# MCU.net
KiCad netlist of a schematic drawn in Altium Designer
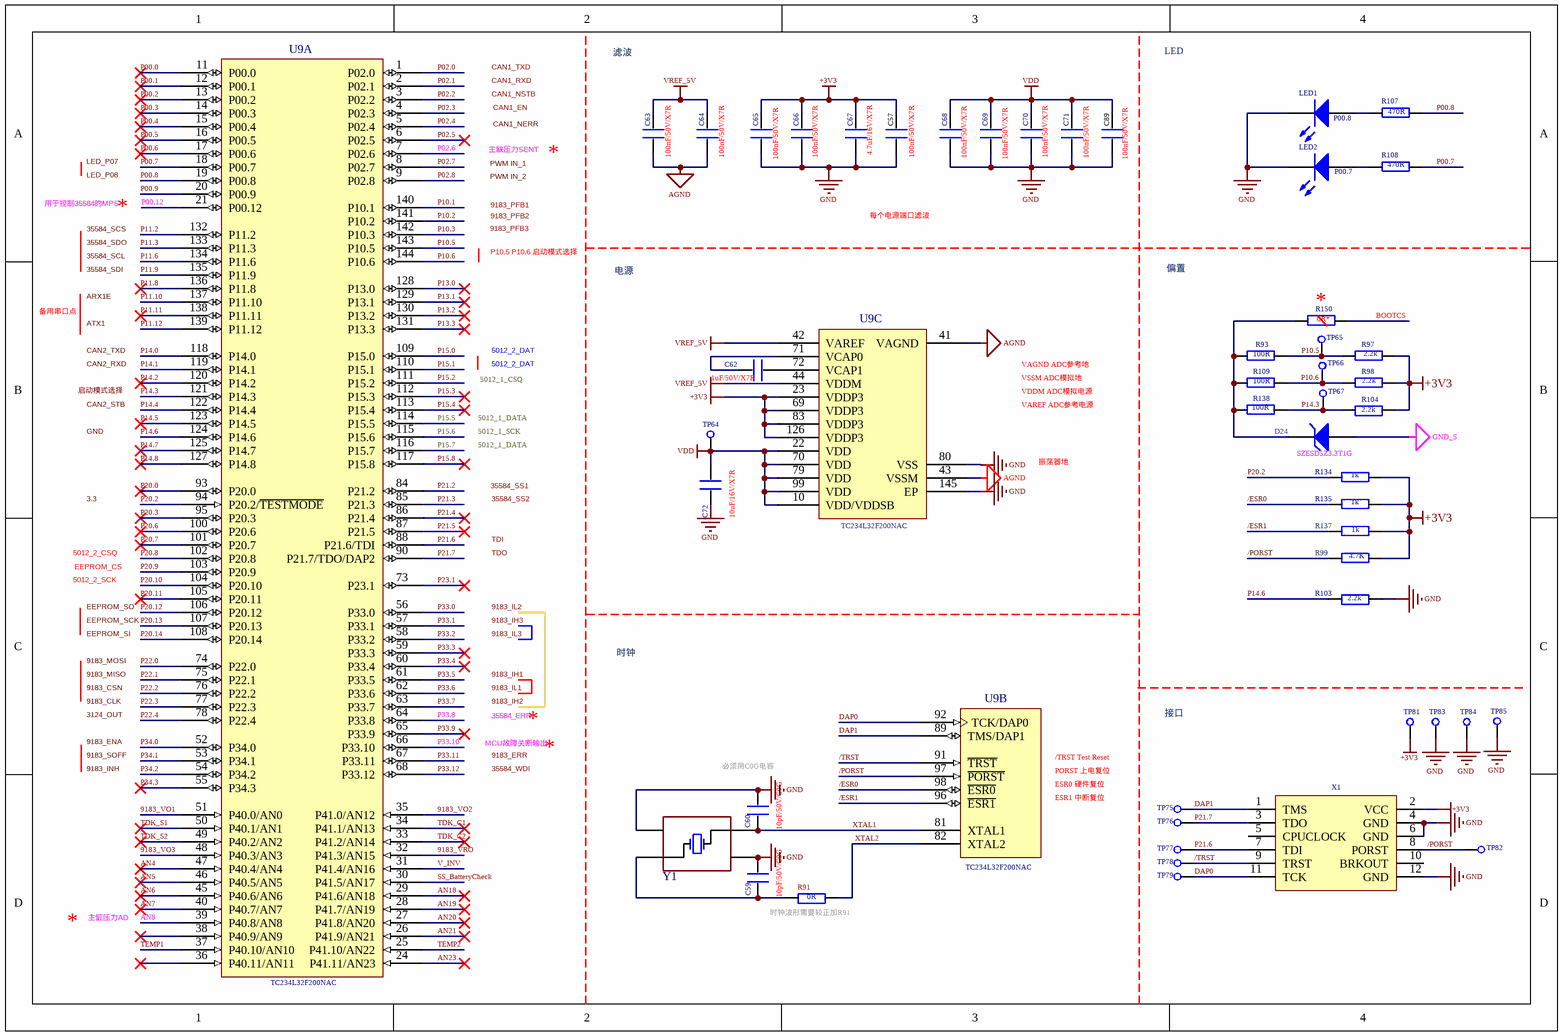
[diagram p0: MCU.SchDoc]

(export (version "E")
  (design (tool "Eeschema 10.0.6"))
  (components
    (comp (ref "C57")
      (value "100nF/50V/X7R")
      (footprint "C0603P")
      (libsource (lib "WarShip V3 STM32103封装库") (part "C"))
    )
    (comp (ref "C59")
      (value "10pF/50V/C0G")
      (footprint "C0603P")
      (libsource (lib "WarShip V3 STM32103封装库") (part "C"))
    )
    (comp (ref "C60")
      (value "10pF/50V/C0G")
      (footprint "C0603P")
      (libsource (lib "WarShip V3 STM32103封装库") (part "C"))
    )
    (comp (ref "C62")
      (value "1uF/50V/X7R")
      (footprint "C0805")
      (libsource (lib "WarShip V3 STM32103封装库") (part "C"))
    )
    (comp (ref "C63")
      (value "100nF/50V/X7R")
      (footprint "C0603P")
      (libsource (lib "WarShip V3 STM32103封装库") (part "C"))
    )
    (comp (ref "C64")
      (value "100nF/50V/X7R")
      (footprint "IEBS_V1.4:C0603P")
      (libsource (lib "WarShip V3 STM32103封装库") (part "C"))
    )
    (comp (ref "C65")
      (value "100nF/50V/X7R")
      (footprint "C0603P")
      (libsource (lib "WarShip V3 STM32103封装库") (part "C"))
    )
    (comp (ref "C66")
      (value "100nF/50V/X7R")
      (footprint "C0603P")
      (libsource (lib "WarShip V3 STM32103封装库") (part "C"))
    )
    (comp (ref "C67")
      (value "4.7uF/16V/X7R")
      (footprint "C0805")
      (libsource (lib "WarShip V3 STM32103封装库") (part "C"))
    )
    (comp (ref "C68")
      (value "100nF/50V/X7R")
      (footprint "C0603P")
      (libsource (lib "WarShip V3 STM32103封装库") (part "C"))
    )
    (comp (ref "C69")
      (value "100nF/50V/X7R")
      (footprint "C0603P")
      (libsource (lib "WarShip V3 STM32103封装库") (part "C"))
    )
    (comp (ref "C70")
      (value "100nF/50V/X7R")
      (footprint "C0603P")
      (libsource (lib "WarShip V3 STM32103封装库") (part "C"))
    )
    (comp (ref "C71")
      (value "100nF/50V/X7R")
      (footprint "C0603P")
      (libsource (lib "WarShip V3 STM32103封装库") (part "C"))
    )
    (comp (ref "C72")
      (value "10uF/16V/X7R")
      (footprint "C1206")
      (libsource (lib "WarShip V3 STM32103封装库") (part "C"))
    )
    (comp (ref "C89")
      (value "100nF/50V/X7R")
      (footprint "C0603P")
      (libsource (lib "WarShip V3 STM32103封装库") (part "C"))
    )
    (comp (ref "D24")
      (value "SZESD5Z3.3T1G")
      (footprint "SOD-523F")
      (description "Zener Diode")
      (fields (field (name "PUBLISHER") "Altium Limited"))
      (libsource (lib "Miscellaneous Devices") (part "D Zener"))
    )
    (comp (ref "LED1")
      (value "P00.8")
      (footprint "LED 0805")
      (description "Typical RED, GREEN, YELLOW, AMBER GaAs LED")
      (fields (field (name "PUBLISHER") "Altium Limited"))
      (libsource (lib "WarShip V3 STM32103封装库") (part "LED2"))
    )
    (comp (ref "LED2")
      (value "P00.7")
      (footprint "LED 0805")
      (description "Typical RED, GREEN, YELLOW, AMBER GaAs LED")
      (fields (field (name "PUBLISHER") "Altium Limited"))
      (libsource (lib "WarShip V3 STM32103封装库") (part "LED2"))
    )
    (comp (ref "R91") (value "0R") (footprint "0603P") (libsource (lib "WarShip V3 STM32103封装库") (part "R")))
    (comp (ref "R93")
      (value "100R")
      (footprint "0603P")
      (libsource (lib "WarShip V3 STM32103封装库") (part "R"))
    )
    (comp (ref "R97")
      (value "2.2k")
      (footprint "0603P")
      (libsource (lib "WarShip V3 STM32103封装库") (part "R"))
    )
    (comp (ref "R98")
      (value "2.2k")
      (footprint "0603P")
      (libsource (lib "WarShip V3 STM32103封装库") (part "R"))
    )
    (comp (ref "R99")
      (value "4.7K")
      (footprint "0603P")
      (libsource (lib "WarShip V3 STM32103封装库") (part "R"))
    )
    (comp (ref "R103")
      (value "2.2k")
      (footprint "0603P")
      (libsource (lib "WarShip V3 STM32103封装库") (part "R"))
    )
    (comp (ref "R104")
      (value "2.2k")
      (footprint "0603P")
      (libsource (lib "WarShip V3 STM32103封装库") (part "R"))
    )
    (comp (ref "R107")
      (value "470R")
      (footprint "0603P")
      (libsource (lib "WarShip V3 STM32103封装库") (part "R"))
    )
    (comp (ref "R108")
      (value "470R")
      (footprint "0603P")
      (libsource (lib "WarShip V3 STM32103封装库") (part "R"))
    )
    (comp (ref "R109")
      (value "100R")
      (footprint "0603P")
      (libsource (lib "WarShip V3 STM32103封装库") (part "R"))
    )
    (comp (ref "R134") (value "1k") (footprint "0603P") (libsource (lib "WarShip V3 STM32103封装库") (part "R")))
    (comp (ref "R135") (value "1k") (footprint "0603P") (libsource (lib "WarShip V3 STM32103封装库") (part "R")))
    (comp (ref "R137") (value "1k") (footprint "0603P") (libsource (lib "WarShip V3 STM32103封装库") (part "R")))
    (comp (ref "R138")
      (value "100R")
      (footprint "0603P")
      (libsource (lib "WarShip V3 STM32103封装库") (part "R"))
    )
    (comp (ref "R150")
      (value "0R*")
      (footprint "0603P")
      (libsource (lib "WarShip V3 STM32103封装库") (part "R"))
    )
    (comp (ref "TP64") (value "测试点") (footprint "测试点") (libsource (lib "yds") (part "测试点")))
    (comp (ref "TP65") (value "测试点") (footprint "测试点") (libsource (lib "yds") (part "测试点")))
    (comp (ref "TP66") (value "测试点") (footprint "测试点") (libsource (lib "yds") (part "测试点")))
    (comp (ref "TP67") (value "测试点") (footprint "测试点") (libsource (lib "yds") (part "测试点")))
    (comp (ref "TP75") (value "测试点") (footprint "测试点") (libsource (lib "yds") (part "测试点")))
    (comp (ref "TP76") (value "测试点") (footprint "测试点") (libsource (lib "yds") (part "测试点")))
    (comp (ref "TP77") (value "测试点") (footprint "测试点") (libsource (lib "yds") (part "测试点")))
    (comp (ref "TP78") (value "测试点") (footprint "测试点") (libsource (lib "yds") (part "测试点")))
    (comp (ref "TP79") (value "测试点") (footprint "测试点") (libsource (lib "yds") (part "测试点")))
    (comp (ref "TP81") (value "测试点") (footprint "测试点") (libsource (lib "yds") (part "测试点")))
    (comp (ref "TP82") (value "测试点") (footprint "测试点") (libsource (lib "yds") (part "测试点")))
    (comp (ref "TP83") (value "测试点") (footprint "测试点") (libsource (lib "yds") (part "测试点")))
    (comp (ref "TP84") (value "测试点") (footprint "测试点") (libsource (lib "yds") (part "测试点")))
    (comp (ref "TP85") (value "测试点") (footprint "测试点") (libsource (lib "yds") (part "测试点")))
    (comp (ref "U9")
      (value "TC234L32F200NAC")
      (footprint "INF-PG-TQFP-144-27_7500X7500TP_V")
      (fields (field (name "PARTNUMBER") "SAK-TC234LA-32F200F AB") (field (name "MANUFACTURER") "Infineon"))
      (libsource (lib "Infineon Microcontroller 32-bit TriCore AURIX") (part "SAK-TC234LA-32F200F AB"))
    )
    (comp (ref "X1") (value "12P") (footprint "HDR2X6 - duplicate") (libsource (lib "myTY") (part "12P")))
    (comp (ref "Y1") (value "晶振") (footprint "OSC-SMD_4P-L3.2-W2.5-BL") (libsource (lib "yds") (part "晶振")))
  )
  (nets
    (net (code "1") (name "+3V3") (class "Default")
      (node (ref "C57") (pin "1") (pintype "passive"))
      (node (ref "C65") (pin "1") (pintype "passive"))
      (node (ref "C66") (pin "1") (pintype "passive"))
      (node (ref "C67") (pin "2") (pintype "passive"))
      (node (ref "R104") (pin "2") (pintype "passive"))
      (node (ref "R134") (pin "1") (pintype "passive"))
      (node (ref "R135") (pin "1") (pintype "passive"))
      (node (ref "R137") (pin "1") (pintype "passive"))
      (node (ref "R97") (pin "1") (pintype "passive"))
      (node (ref "R98") (pin "1") (pintype "passive"))
      (node (ref "R99") (pin "1") (pintype "passive"))
      (node (ref "TP81") (pin "1") (pinfunction "1_1") (pintype "passive"))
      (node (ref "U9") (pin "126") (pinfunction "VDDP3_126") (pintype "power_in"))
      (node (ref "U9") (pin "23") (pinfunction "VDDP3_23") (pintype "power_in"))
      (node (ref "U9") (pin "69") (pinfunction "VDDP3_69") (pintype "power_in"))
      (node (ref "U9") (pin "83") (pinfunction "VDDP3_83") (pintype "power_in"))
      (node (ref "X1") (pin "2") (pinfunction "VCC_2") (pintype "passive"))
    )
    (net (code "5") (name "/9183_VO1") (class "Default")
      (node (ref "U9") (pin "51") (pinfunction "P40.0/AN0_51") (pintype "input"))
    )
    (net (code "6") (name "/9183_VO2") (class "Default")
      (node (ref "U9") (pin "35") (pinfunction "P41.0/AN12_35") (pintype "input"))
    )
    (net (code "7") (name "/9183_VO3") (class "Default")
      (node (ref "U9") (pin "48") (pinfunction "P40.3/AN3_48") (pintype "input"))
    )
    (net (code "8") (name "/9183_VRO") (class "Default")
      (node (ref "U9") (pin "32") (pinfunction "P41.3/AN15_32") (pintype "input"))
    )
    (net (code "9") (name "/AN4") (class "Default")
      (node (ref "U9") (pin "47") (pinfunction "P40.4/AN4_47") (pintype "input+no_connect"))
    )
    (net (code "10") (name "/AN5") (class "Default")
      (node (ref "U9") (pin "46") (pinfunction "P40.5/AN5_46") (pintype "input+no_connect"))
    )
    (net (code "11") (name "/AN6") (class "Default")
      (node (ref "U9") (pin "45") (pinfunction "P40.6/AN6_45") (pintype "input+no_connect"))
    )
    (net (code "12") (name "/AN7") (class "Default")
      (node (ref "U9") (pin "40") (pinfunction "P40.7/AN7_40") (pintype "input+no_connect"))
    )
    (net (code "13") (name "/AN8") (class "Default")
      (node (ref "U9") (pin "39") (pinfunction "P40.8/AN8_39") (pintype "input"))
    )
    (net (code "14") (name "/AN18") (class "Default")
      (node (ref "U9") (pin "29") (pinfunction "P41.6/AN18_29") (pintype "input+no_connect"))
    )
    (net (code "15") (name "/AN19") (class "Default")
      (node (ref "U9") (pin "28") (pinfunction "P41.7/AN19_28") (pintype "input+no_connect"))
    )
    (net (code "16") (name "/AN20") (class "Default")
      (node (ref "U9") (pin "27") (pinfunction "P41.8/AN20_27") (pintype "input+no_connect"))
    )
    (net (code "17") (name "/AN21") (class "Default")
      (node (ref "U9") (pin "26") (pinfunction "P41.9/AN21_26") (pintype "input+no_connect"))
    )
    (net (code "18") (name "/AN23") (class "Default")
      (node (ref "U9") (pin "24") (pinfunction "P41.11/AN23_24") (pintype "input+no_connect"))
    )
    (net (code "19") (name "/BOOTCS") (class "Default") (node (ref "R150") (pin "1") (pintype "passive")))
    (net (code "20") (name "/DAP0") (class "Default")
      (node (ref "TP79") (pin "1") (pinfunction "1_1") (pintype "passive"))
      (node (ref "U9") (pin "92") (pinfunction "TCK/DAP0_92") (pintype "input"))
      (node (ref "X1") (pin "11") (pinfunction "TCK_11") (pintype "passive"))
    )
    (net (code "21") (name "/DAP1") (class "Default")
      (node (ref "TP75") (pin "1") (pinfunction "1_1") (pintype "passive"))
      (node (ref "U9") (pin "89") (pinfunction "TMS/DAP1_89") (pintype "bidirectional"))
      (node (ref "X1") (pin "1") (pinfunction "TMS_1") (pintype "passive"))
    )
    (net (code "22") (name "/P00.0") (class "Default")
      (node (ref "U9") (pin "11") (pinfunction "P00.0_11") (pintype "bidirectional+no_connect"))
    )
    (net (code "23") (name "/P00.1") (class "Default")
      (node (ref "U9") (pin "12") (pinfunction "P00.1_12") (pintype "bidirectional+no_connect"))
    )
    (net (code "24") (name "/P00.2") (class "Default")
      (node (ref "U9") (pin "13") (pinfunction "P00.2_13") (pintype "bidirectional+no_connect"))
    )
    (net (code "25") (name "/P00.3") (class "Default")
      (node (ref "U9") (pin "14") (pinfunction "P00.3_14") (pintype "bidirectional+no_connect"))
    )
    (net (code "26") (name "/P00.4") (class "Default")
      (node (ref "U9") (pin "15") (pinfunction "P00.4_15") (pintype "bidirectional+no_connect"))
    )
    (net (code "27") (name "/P00.5") (class "Default")
      (node (ref "U9") (pin "16") (pinfunction "P00.5_16") (pintype "bidirectional+no_connect"))
    )
    (net (code "28") (name "/P00.6") (class "Default")
      (node (ref "U9") (pin "17") (pinfunction "P00.6_17") (pintype "bidirectional+no_connect"))
    )
    (net (code "29") (name "/P00.7") (class "Default")
      (node (ref "R108") (pin "1") (pintype "passive"))
      (node (ref "U9") (pin "18") (pinfunction "P00.7_18") (pintype "bidirectional"))
    )
    (net (code "30") (name "/P00.8") (class "Default")
      (node (ref "R107") (pin "1") (pintype "passive"))
      (node (ref "U9") (pin "19") (pinfunction "P00.8_19") (pintype "bidirectional"))
    )
    (net (code "31") (name "/P00.9") (class "Default")
      (node (ref "U9") (pin "20") (pinfunction "P00.9_20") (pintype "bidirectional"))
    )
    (net (code "32") (name "/P00.12") (class "Default")
      (node (ref "U9") (pin "21") (pinfunction "P00.12_21") (pintype "bidirectional"))
    )
    (net (code "33") (name "/P02.0") (class "Default")
      (node (ref "U9") (pin "1") (pinfunction "P02.0_1") (pintype "bidirectional"))
    )
    (net (code "34") (name "/P02.1") (class "Default")
      (node (ref "U9") (pin "2") (pinfunction "P02.1_2") (pintype "bidirectional"))
    )
    (net (code "35") (name "/P02.2") (class "Default")
      (node (ref "U9") (pin "3") (pinfunction "P02.2_3") (pintype "bidirectional"))
    )
    (net (code "36") (name "/P02.3") (class "Default")
      (node (ref "U9") (pin "4") (pinfunction "P02.3_4") (pintype "bidirectional"))
    )
    (net (code "37") (name "/P02.4") (class "Default")
      (node (ref "U9") (pin "5") (pinfunction "P02.4_5") (pintype "bidirectional"))
    )
    (net (code "38") (name "/P02.5") (class "Default")
      (node (ref "U9") (pin "6") (pinfunction "P02.5_6") (pintype "bidirectional+no_connect"))
    )
    (net (code "39") (name "/P02.6") (class "Default")
      (node (ref "U9") (pin "7") (pinfunction "P02.6_7") (pintype "bidirectional"))
    )
    (net (code "40") (name "/P02.7") (class "Default")
      (node (ref "U9") (pin "8") (pinfunction "P02.7_8") (pintype "bidirectional"))
    )
    (net (code "41") (name "/P02.8") (class "Default")
      (node (ref "U9") (pin "9") (pinfunction "P02.8_9") (pintype "bidirectional"))
    )
    (net (code "42") (name "/P10.1") (class "Default")
      (node (ref "U9") (pin "140") (pinfunction "P10.1_140") (pintype "bidirectional"))
    )
    (net (code "43") (name "/P10.2") (class "Default")
      (node (ref "U9") (pin "141") (pinfunction "P10.2_141") (pintype "bidirectional"))
    )
    (net (code "44") (name "/P10.3") (class "Default")
      (node (ref "U9") (pin "142") (pinfunction "P10.3_142") (pintype "bidirectional"))
    )
    (net (code "45") (name "/P10.5") (class "Default")
      (node (ref "R93") (pin "1") (pintype "passive"))
      (node (ref "R97") (pin "2") (pintype "passive"))
      (node (ref "TP65") (pin "1") (pinfunction "1_1") (pintype "passive"))
      (node (ref "U9") (pin "143") (pinfunction "P10.5_143") (pintype "bidirectional"))
    )
    (net (code "46") (name "/P10.6") (class "Default")
      (node (ref "R109") (pin "1") (pintype "passive"))
      (node (ref "R98") (pin "2") (pintype "passive"))
      (node (ref "TP66") (pin "1") (pinfunction "1_1") (pintype "passive"))
      (node (ref "U9") (pin "144") (pinfunction "P10.6_144") (pintype "bidirectional"))
    )
    (net (code "47") (name "/P11.2") (class "Default")
      (node (ref "U9") (pin "132") (pinfunction "P11.2_132") (pintype "bidirectional"))
    )
    (net (code "48") (name "/P11.3") (class "Default")
      (node (ref "U9") (pin "133") (pinfunction "P11.3_133") (pintype "bidirectional"))
    )
    (net (code "49") (name "/P11.6") (class "Default")
      (node (ref "U9") (pin "134") (pinfunction "P11.6_134") (pintype "bidirectional"))
    )
    (net (code "50") (name "/P11.8") (class "Default")
      (node (ref "U9") (pin "136") (pinfunction "P11.8_136") (pintype "bidirectional+no_connect"))
    )
    (net (code "51") (name "/P11.9") (class "Default")
      (node (ref "U9") (pin "135") (pinfunction "P11.9_135") (pintype "bidirectional"))
    )
    (net (code "52") (name "/P11.10") (class "Default")
      (node (ref "U9") (pin "137") (pinfunction "P11.10_137") (pintype "bidirectional"))
    )
    (net (code "53") (name "/P11.11") (class "Default")
      (node (ref "U9") (pin "138") (pinfunction "P11.11_138") (pintype "bidirectional+no_connect"))
    )
    (net (code "54") (name "/P11.12") (class "Default")
      (node (ref "U9") (pin "139") (pinfunction "P11.12_139") (pintype "bidirectional"))
    )
    (net (code "55") (name "/P13.0") (class "Default")
      (node (ref "U9") (pin "128") (pinfunction "P13.0_128") (pintype "bidirectional+no_connect"))
    )
    (net (code "56") (name "/P13.1") (class "Default")
      (node (ref "U9") (pin "129") (pinfunction "P13.1_129") (pintype "bidirectional+no_connect"))
    )
    (net (code "57") (name "/P13.2") (class "Default")
      (node (ref "U9") (pin "130") (pinfunction "P13.2_130") (pintype "bidirectional+no_connect"))
    )
    (net (code "58") (name "/P13.3") (class "Default")
      (node (ref "U9") (pin "131") (pinfunction "P13.3_131") (pintype "bidirectional+no_connect"))
    )
    (net (code "59") (name "/P14.0") (class "Default")
      (node (ref "U9") (pin "118") (pinfunction "P14.0_118") (pintype "bidirectional"))
    )
    (net (code "60") (name "/P14.1") (class "Default")
      (node (ref "U9") (pin "119") (pinfunction "P14.1_119") (pintype "bidirectional"))
    )
    (net (code "61") (name "/P14.2") (class "Default")
      (node (ref "U9") (pin "120") (pinfunction "P14.2_120") (pintype "bidirectional+no_connect"))
    )
    (net (code "62") (name "/P14.3") (class "Default")
      (node (ref "R104") (pin "1") (pintype "passive"))
      (node (ref "R138") (pin "1") (pintype "passive"))
      (node (ref "TP67") (pin "1") (pinfunction "1_1") (pintype "passive"))
      (node (ref "U9") (pin "121") (pinfunction "P14.3_121") (pintype "bidirectional"))
    )
    (net (code "63") (name "/P14.4") (class "Default")
      (node (ref "U9") (pin "122") (pinfunction "P14.4_122") (pintype "bidirectional"))
    )
    (net (code "64") (name "/P14.5") (class "Default")
      (node (ref "U9") (pin "123") (pinfunction "P14.5_123") (pintype "bidirectional+no_connect"))
    )
    (net (code "65") (name "/P14.6") (class "Default")
      (node (ref "R103") (pin "1") (pintype "passive"))
      (node (ref "U9") (pin "124") (pinfunction "P14.6_124") (pintype "bidirectional"))
    )
    (net (code "66") (name "/P14.7") (class "Default")
      (node (ref "U9") (pin "125") (pinfunction "P14.7_125") (pintype "bidirectional+no_connect"))
    )
    (net (code "67") (name "/P14.8") (class "Default")
      (node (ref "U9") (pin "127") (pinfunction "P14.8_127") (pintype "bidirectional+no_connect"))
    )
    (net (code "68") (name "/P15.0") (class "Default")
      (node (ref "U9") (pin "109") (pinfunction "P15.0_109") (pintype "bidirectional"))
    )
    (net (code "69") (name "/P15.1") (class "Default")
      (node (ref "U9") (pin "110") (pinfunction "P15.1_110") (pintype "bidirectional"))
    )
    (net (code "70") (name "/P15.2") (class "Default")
      (node (ref "U9") (pin "111") (pinfunction "P15.2_111") (pintype "bidirectional"))
    )
    (net (code "71") (name "/P15.3") (class "Default")
      (node (ref "U9") (pin "112") (pinfunction "P15.3_112") (pintype "bidirectional+no_connect"))
    )
    (net (code "72") (name "/P15.4") (class "Default")
      (node (ref "U9") (pin "113") (pinfunction "P15.4_113") (pintype "bidirectional+no_connect"))
    )
    (net (code "73") (name "/P15.5") (class "Default")
      (node (ref "U9") (pin "114") (pinfunction "P15.5_114") (pintype "bidirectional"))
    )
    (net (code "74") (name "/P15.6") (class "Default")
      (node (ref "U9") (pin "115") (pinfunction "P15.6_115") (pintype "bidirectional"))
    )
    (net (code "75") (name "/P15.7") (class "Default")
      (node (ref "U9") (pin "116") (pinfunction "P15.7_116") (pintype "bidirectional"))
    )
    (net (code "76") (name "/P15.8") (class "Default")
      (node (ref "U9") (pin "117") (pinfunction "P15.8_117") (pintype "bidirectional+no_connect"))
    )
    (net (code "77") (name "/P20.0") (class "Default")
      (node (ref "U9") (pin "93") (pinfunction "P20.0_93") (pintype "bidirectional+no_connect"))
    )
    (net (code "78") (name "/P20.2") (class "Default")
      (node (ref "R134") (pin "2") (pintype "passive"))
      (node (ref "U9") (pin "94") (pinfunction "P20.2/~{TESTMODE}_94") (pintype "input"))
    )
    (net (code "79") (name "/P20.3") (class "Default")
      (node (ref "U9") (pin "95") (pinfunction "P20.3_95") (pintype "bidirectional+no_connect"))
    )
    (net (code "80") (name "/P20.6") (class "Default")
      (node (ref "U9") (pin "100") (pinfunction "P20.6_100") (pintype "bidirectional+no_connect"))
    )
    (net (code "81") (name "/P20.7") (class "Default")
      (node (ref "U9") (pin "101") (pinfunction "P20.7_101") (pintype "bidirectional+no_connect"))
    )
    (net (code "82") (name "/P20.8") (class "Default")
      (node (ref "U9") (pin "102") (pinfunction "P20.8_102") (pintype "bidirectional"))
    )
    (net (code "83") (name "/P20.9") (class "Default")
      (node (ref "U9") (pin "103") (pinfunction "P20.9_103") (pintype "bidirectional"))
    )
    (net (code "84") (name "/P20.10") (class "Default")
      (node (ref "U9") (pin "104") (pinfunction "P20.10_104") (pintype "bidirectional"))
    )
    (net (code "85") (name "/P20.11") (class "Default")
      (node (ref "U9") (pin "105") (pinfunction "P20.11_105") (pintype "bidirectional+no_connect"))
    )
    (net (code "86") (name "/P20.12") (class "Default")
      (node (ref "U9") (pin "106") (pinfunction "P20.12_106") (pintype "bidirectional"))
    )
    (net (code "87") (name "/P20.13") (class "Default")
      (node (ref "U9") (pin "107") (pinfunction "P20.13_107") (pintype "bidirectional"))
    )
    (net (code "88") (name "/P20.14") (class "Default")
      (node (ref "U9") (pin "108") (pinfunction "P20.14_108") (pintype "bidirectional"))
    )
    (net (code "89") (name "/P21.2") (class "Default")
      (node (ref "U9") (pin "84") (pinfunction "P21.2_84") (pintype "bidirectional"))
    )
    (net (code "90") (name "/P21.3") (class "Default")
      (node (ref "U9") (pin "85") (pinfunction "P21.3_85") (pintype "bidirectional"))
    )
    (net (code "91") (name "/P21.4") (class "Default")
      (node (ref "U9") (pin "86") (pinfunction "P21.4_86") (pintype "bidirectional+no_connect"))
    )
    (net (code "92") (name "/P21.5") (class "Default")
      (node (ref "U9") (pin "87") (pinfunction "P21.5_87") (pintype "bidirectional+no_connect"))
    )
    (net (code "93") (name "/P21.6") (class "Default")
      (node (ref "TP77") (pin "1") (pinfunction "1_1") (pintype "passive"))
      (node (ref "U9") (pin "88") (pinfunction "P21.6/TDI_88") (pintype "bidirectional"))
      (node (ref "X1") (pin "7") (pinfunction "TDI_7") (pintype "passive"))
    )
    (net (code "94") (name "/P21.7") (class "Default")
      (node (ref "TP76") (pin "1") (pinfunction "1_1") (pintype "passive"))
      (node (ref "U9") (pin "90") (pinfunction "P21.7/TDO/DAP2_90") (pintype "bidirectional"))
      (node (ref "X1") (pin "3") (pinfunction "TDO_3") (pintype "passive"))
    )
    (net (code "95") (name "/P22.0") (class "Default")
      (node (ref "U9") (pin "74") (pinfunction "P22.0_74") (pintype "bidirectional"))
    )
    (net (code "96") (name "/P22.1") (class "Default")
      (node (ref "U9") (pin "75") (pinfunction "P22.1_75") (pintype "bidirectional"))
    )
    (net (code "97") (name "/P22.2") (class "Default")
      (node (ref "U9") (pin "76") (pinfunction "P22.2_76") (pintype "bidirectional"))
    )
    (net (code "98") (name "/P22.3") (class "Default")
      (node (ref "U9") (pin "77") (pinfunction "P22.3_77") (pintype "bidirectional"))
    )
    (net (code "99") (name "/P22.4") (class "Default")
      (node (ref "U9") (pin "78") (pinfunction "P22.4_78") (pintype "bidirectional"))
    )
    (net (code "100") (name "/P23.1") (class "Default")
      (node (ref "U9") (pin "73") (pinfunction "P23.1_73") (pintype "bidirectional+no_connect"))
    )
    (net (code "101") (name "/P33.0") (class "Default")
      (node (ref "U9") (pin "56") (pinfunction "P33.0_56") (pintype "bidirectional"))
    )
    (net (code "102") (name "/P33.1") (class "Default")
      (node (ref "U9") (pin "57") (pinfunction "P33.1_57") (pintype "bidirectional"))
    )
    (net (code "103") (name "/P33.2") (class "Default")
      (node (ref "U9") (pin "58") (pinfunction "P33.2_58") (pintype "bidirectional"))
    )
    (net (code "104") (name "/P33.3") (class "Default")
      (node (ref "U9") (pin "59") (pinfunction "P33.3_59") (pintype "bidirectional+no_connect"))
    )
    (net (code "105") (name "/P33.4") (class "Default")
      (node (ref "U9") (pin "60") (pinfunction "P33.4_60") (pintype "bidirectional+no_connect"))
    )
    (net (code "106") (name "/P33.5") (class "Default")
      (node (ref "U9") (pin "61") (pinfunction "P33.5_61") (pintype "bidirectional"))
    )
    (net (code "107") (name "/P33.6") (class "Default")
      (node (ref "U9") (pin "62") (pinfunction "P33.6_62") (pintype "bidirectional"))
    )
    (net (code "108") (name "/P33.7") (class "Default")
      (node (ref "U9") (pin "63") (pinfunction "P33.7_63") (pintype "bidirectional"))
    )
    (net (code "109") (name "/P33.8") (class "Default")
      (node (ref "U9") (pin "64") (pinfunction "P33.8_64") (pintype "bidirectional"))
    )
    (net (code "110") (name "/P33.9") (class "Default")
      (node (ref "U9") (pin "65") (pinfunction "P33.9_65") (pintype "bidirectional+no_connect"))
    )
    (net (code "111") (name "/P33.10") (class "Default")
      (node (ref "U9") (pin "66") (pinfunction "P33.10_66") (pintype "bidirectional"))
    )
    (net (code "112") (name "/P33.11") (class "Default")
      (node (ref "U9") (pin "67") (pinfunction "P33.11_67") (pintype "bidirectional"))
    )
    (net (code "113") (name "/P33.12") (class "Default")
      (node (ref "U9") (pin "68") (pinfunction "P33.12_68") (pintype "bidirectional"))
    )
    (net (code "114") (name "/P34.0") (class "Default")
      (node (ref "U9") (pin "52") (pinfunction "P34.0_52") (pintype "bidirectional"))
    )
    (net (code "115") (name "/P34.1") (class "Default")
      (node (ref "U9") (pin "53") (pinfunction "P34.1_53") (pintype "bidirectional"))
    )
    (net (code "116") (name "/P34.2") (class "Default")
      (node (ref "U9") (pin "54") (pinfunction "P34.2_54") (pintype "bidirectional"))
    )
    (net (code "117") (name "/P34.3") (class "Default")
      (node (ref "U9") (pin "55") (pinfunction "P34.3_55") (pintype "bidirectional+no_connect"))
    )
    (net (code "118") (name "/SS_BatteryCheck") (class "Default")
      (node (ref "U9") (pin "30") (pinfunction "P41.5/AN17_30") (pintype "input"))
    )
    (net (code "119") (name "/TDK_C1") (class "Default")
      (node (ref "U9") (pin "34") (pinfunction "P41.1/AN13_34") (pintype "input+no_connect"))
    )
    (net (code "120") (name "/TDK_C2") (class "Default")
      (node (ref "U9") (pin "33") (pinfunction "P41.2/AN14_33") (pintype "input+no_connect"))
    )
    (net (code "121") (name "/TDK_S1") (class "Default")
      (node (ref "U9") (pin "50") (pinfunction "P40.1/AN1_50") (pintype "input+no_connect"))
    )
    (net (code "122") (name "/TDK_S2") (class "Default")
      (node (ref "U9") (pin "49") (pinfunction "P40.2/AN2_49") (pintype "input+no_connect"))
    )
    (net (code "123") (name "/TEMP1") (class "Default")
      (node (ref "U9") (pin "37") (pinfunction "P40.10/AN10_37") (pintype "input"))
    )
    (net (code "124") (name "/TEMP2") (class "Default")
      (node (ref "U9") (pin "25") (pinfunction "P41.10/AN22_25") (pintype "input"))
    )
    (net (code "125") (name "/V_INV") (class "Default")
      (node (ref "U9") (pin "31") (pinfunction "P41.4/AN16_31") (pintype "input"))
    )
    (net (code "126") (name "/XTAL1") (class "Default")
      (node (ref "C60") (pin "1") (pintype "passive"))
      (node (ref "U9") (pin "81") (pinfunction "XTAL1_81") (pintype "passive"))
      (node (ref "Y1") (pin "1") (pinfunction "OSC1_1") (pintype "passive"))
    )
    (net (code "127") (name "/XTAL2") (class "Default")
      (node (ref "R91") (pin "2") (pintype "passive"))
      (node (ref "U9") (pin "82") (pinfunction "XTAL2_82") (pintype "passive"))
    )
    (net (code "128") (name "/{slash}ESR0") (class "Default")
      (node (ref "R135") (pin "2") (pintype "passive"))
      (node (ref "U9") (pin "98") (pinfunction "~{ESR0}_98") (pintype "bidirectional"))
    )
    (net (code "129") (name "/{slash}ESR1") (class "Default")
      (node (ref "R137") (pin "2") (pintype "passive"))
      (node (ref "U9") (pin "96") (pinfunction "~{ESR1}_96") (pintype "bidirectional"))
    )
    (net (code "130") (name "/{slash}PORST") (class "Default")
      (node (ref "R99") (pin "2") (pintype "passive"))
      (node (ref "TP82") (pin "1") (pinfunction "1_1") (pintype "passive"))
      (node (ref "U9") (pin "97") (pinfunction "~{PORST}_97") (pintype "input"))
      (node (ref "X1") (pin "8") (pinfunction "PORST_8") (pintype "passive"))
    )
    (net (code "131") (name "/{slash}TRST") (class "Default")
      (node (ref "TP78") (pin "1") (pinfunction "1_1") (pintype "passive"))
      (node (ref "U9") (pin "91") (pinfunction "~{TRST}_91") (pintype "input"))
      (node (ref "X1") (pin "9") (pinfunction "TRST_9") (pintype "passive"))
    )
    (net (code "132") (name "AGND") (class "Default")
      (node (ref "C63") (pin "2") (pintype "passive"))
      (node (ref "C64") (pin "2") (pintype "passive"))
      (node (ref "U9") (pin "41") (pinfunction "VAGND_41") (pintype "power_in"))
      (node (ref "U9") (pin "43") (pinfunction "VSSM_43") (pintype "power_in"))
    )
    (net (code "133") (name "GND") (class "Default")
      (node (ref "C57") (pin "2") (pintype "passive"))
      (node (ref "C59") (pin "2") (pintype "passive"))
      (node (ref "C60") (pin "2") (pintype "passive"))
      (node (ref "C65") (pin "2") (pintype "passive"))
      (node (ref "C66") (pin "2") (pintype "passive"))
      (node (ref "C67") (pin "1") (pintype "passive"))
      (node (ref "C68") (pin "2") (pintype "passive"))
      (node (ref "C69") (pin "2") (pintype "passive"))
      (node (ref "C70") (pin "2") (pintype "passive"))
      (node (ref "C71") (pin "2") (pintype "passive"))
      (node (ref "C72") (pin "1") (pintype "passive"))
      (node (ref "C89") (pin "2") (pintype "passive"))
      (node (ref "LED1") (pin "2") (pinfunction "K_2") (pintype "passive"))
      (node (ref "LED2") (pin "2") (pinfunction "K_2") (pintype "passive"))
      (node (ref "R103") (pin "2") (pintype "passive"))
      (node (ref "TP83") (pin "1") (pinfunction "1_1") (pintype "passive"))
      (node (ref "TP84") (pin "1") (pinfunction "1_1") (pintype "passive"))
      (node (ref "TP85") (pin "1") (pinfunction "1_1") (pintype "passive"))
      (node (ref "U9") (pin "145") (pinfunction "EP_145") (pintype "power_in"))
      (node (ref "U9") (pin "80") (pinfunction "VSS_80") (pintype "power_in"))
      (node (ref "X1") (pin "12") (pinfunction "GND_12") (pintype "passive"))
      (node (ref "X1") (pin "4") (pinfunction "GND_4") (pintype "passive"))
      (node (ref "X1") (pin "6") (pinfunction "GND_6") (pintype "passive"))
      (node (ref "Y1") (pin "2") (pinfunction "GND_2") (pintype "passive"))
      (node (ref "Y1") (pin "4") (pinfunction "GND_4") (pintype "passive"))
    )
    (net (code "134") (name "GND_S") (class "Default")
      (node (ref "D24") (pin "2") (pinfunction "A_2") (pintype "passive"))
    )
    (net (code "135") (name "Net-(D24-K)") (class "Default")
      (node (ref "D24") (pin "1") (pinfunction "K_1") (pintype "passive"))
      (node (ref "R109") (pin "2") (pintype "passive"))
      (node (ref "R138") (pin "2") (pintype "passive"))
      (node (ref "R150") (pin "2") (pintype "passive"))
      (node (ref "R93") (pin "2") (pintype "passive"))
    )
    (net (code "136") (name "Net-(LED1-A)") (class "Default")
      (node (ref "LED1") (pin "1") (pinfunction "A_1") (pintype "passive"))
      (node (ref "R107") (pin "2") (pintype "passive"))
    )
    (net (code "137") (name "Net-(LED2-A)") (class "Default")
      (node (ref "LED2") (pin "1") (pinfunction "A_1") (pintype "passive"))
      (node (ref "R108") (pin "2") (pintype "passive"))
    )
    (net (code "138") (name "Net-(U9C-VCAP0)") (class "Default")
      (node (ref "C62") (pin "1") (pintype "passive"))
      (node (ref "U9") (pin "71") (pinfunction "VCAP0_71") (pintype "power_in"))
    )
    (net (code "139") (name "Net-(U9C-VCAP1)") (class "Default")
      (node (ref "C62") (pin "2") (pintype "passive"))
      (node (ref "U9") (pin "72") (pinfunction "VCAP1_72") (pintype "power_in"))
    )
    (net (code "140") (name "Net-(Y1-OSC2)") (class "Default")
      (node (ref "C59") (pin "1") (pintype "passive"))
      (node (ref "R91") (pin "1") (pintype "passive"))
      (node (ref "Y1") (pin "3") (pinfunction "OSC2_3") (pintype "passive"))
    )
    (net (code "141") (name "VDD") (class "Default")
      (node (ref "C68") (pin "1") (pintype "passive"))
      (node (ref "C69") (pin "1") (pintype "passive"))
      (node (ref "C70") (pin "1") (pintype "passive"))
      (node (ref "C71") (pin "1") (pintype "passive"))
      (node (ref "C72") (pin "2") (pintype "passive"))
      (node (ref "C89") (pin "1") (pintype "passive"))
      (node (ref "TP64") (pin "1") (pinfunction "1_1") (pintype "passive"))
      (node (ref "U9") (pin "10") (pinfunction "VDD/VDDSB_10") (pintype "power_in"))
      (node (ref "U9") (pin "22") (pinfunction "VDD_22") (pintype "power_in"))
      (node (ref "U9") (pin "70") (pinfunction "VDD_70") (pintype "power_in"))
      (node (ref "U9") (pin "79") (pinfunction "VDD_79") (pintype "power_in"))
      (node (ref "U9") (pin "99") (pinfunction "VDD_99") (pintype "power_in"))
    )
    (net (code "142") (name "VREF_5V") (class "Default")
      (node (ref "C63") (pin "1") (pintype "passive"))
      (node (ref "C64") (pin "1") (pintype "passive"))
      (node (ref "U9") (pin "42") (pinfunction "VAREF_42") (pintype "power_in"))
      (node (ref "U9") (pin "44") (pinfunction "VDDM_44") (pintype "power_in"))
    )
    (net (code "143") (name "unconnected-(U9A-P40.9{slash}AN9-Pad38)") (class "Default")
      (node (ref "U9") (pin "38") (pinfunction "P40.9/AN9_38") (pintype "input+no_connect"))
    )
    (net (code "144") (name "unconnected-(U9A-P40.11{slash}AN11-Pad36)") (class "Default")
      (node (ref "U9") (pin "36") (pinfunction "P40.11/AN11_36") (pintype "input+no_connect"))
    )
    (net (code "145") (name "unconnected-(X1-BRKOUT-Pad10)") (class "Default")
      (node (ref "X1") (pin "10") (pinfunction "BRKOUT_10") (pintype "passive"))
    )
    (net (code "146") (name "unconnected-(X1-CPUCLOCK-Pad5)") (class "Default")
      (node (ref "X1") (pin "5") (pinfunction "CPUCLOCK_5") (pintype "passive"))
    )
  )
)
